# hotswap.net
KiCad netlist of a schematic drawn in EAGLE
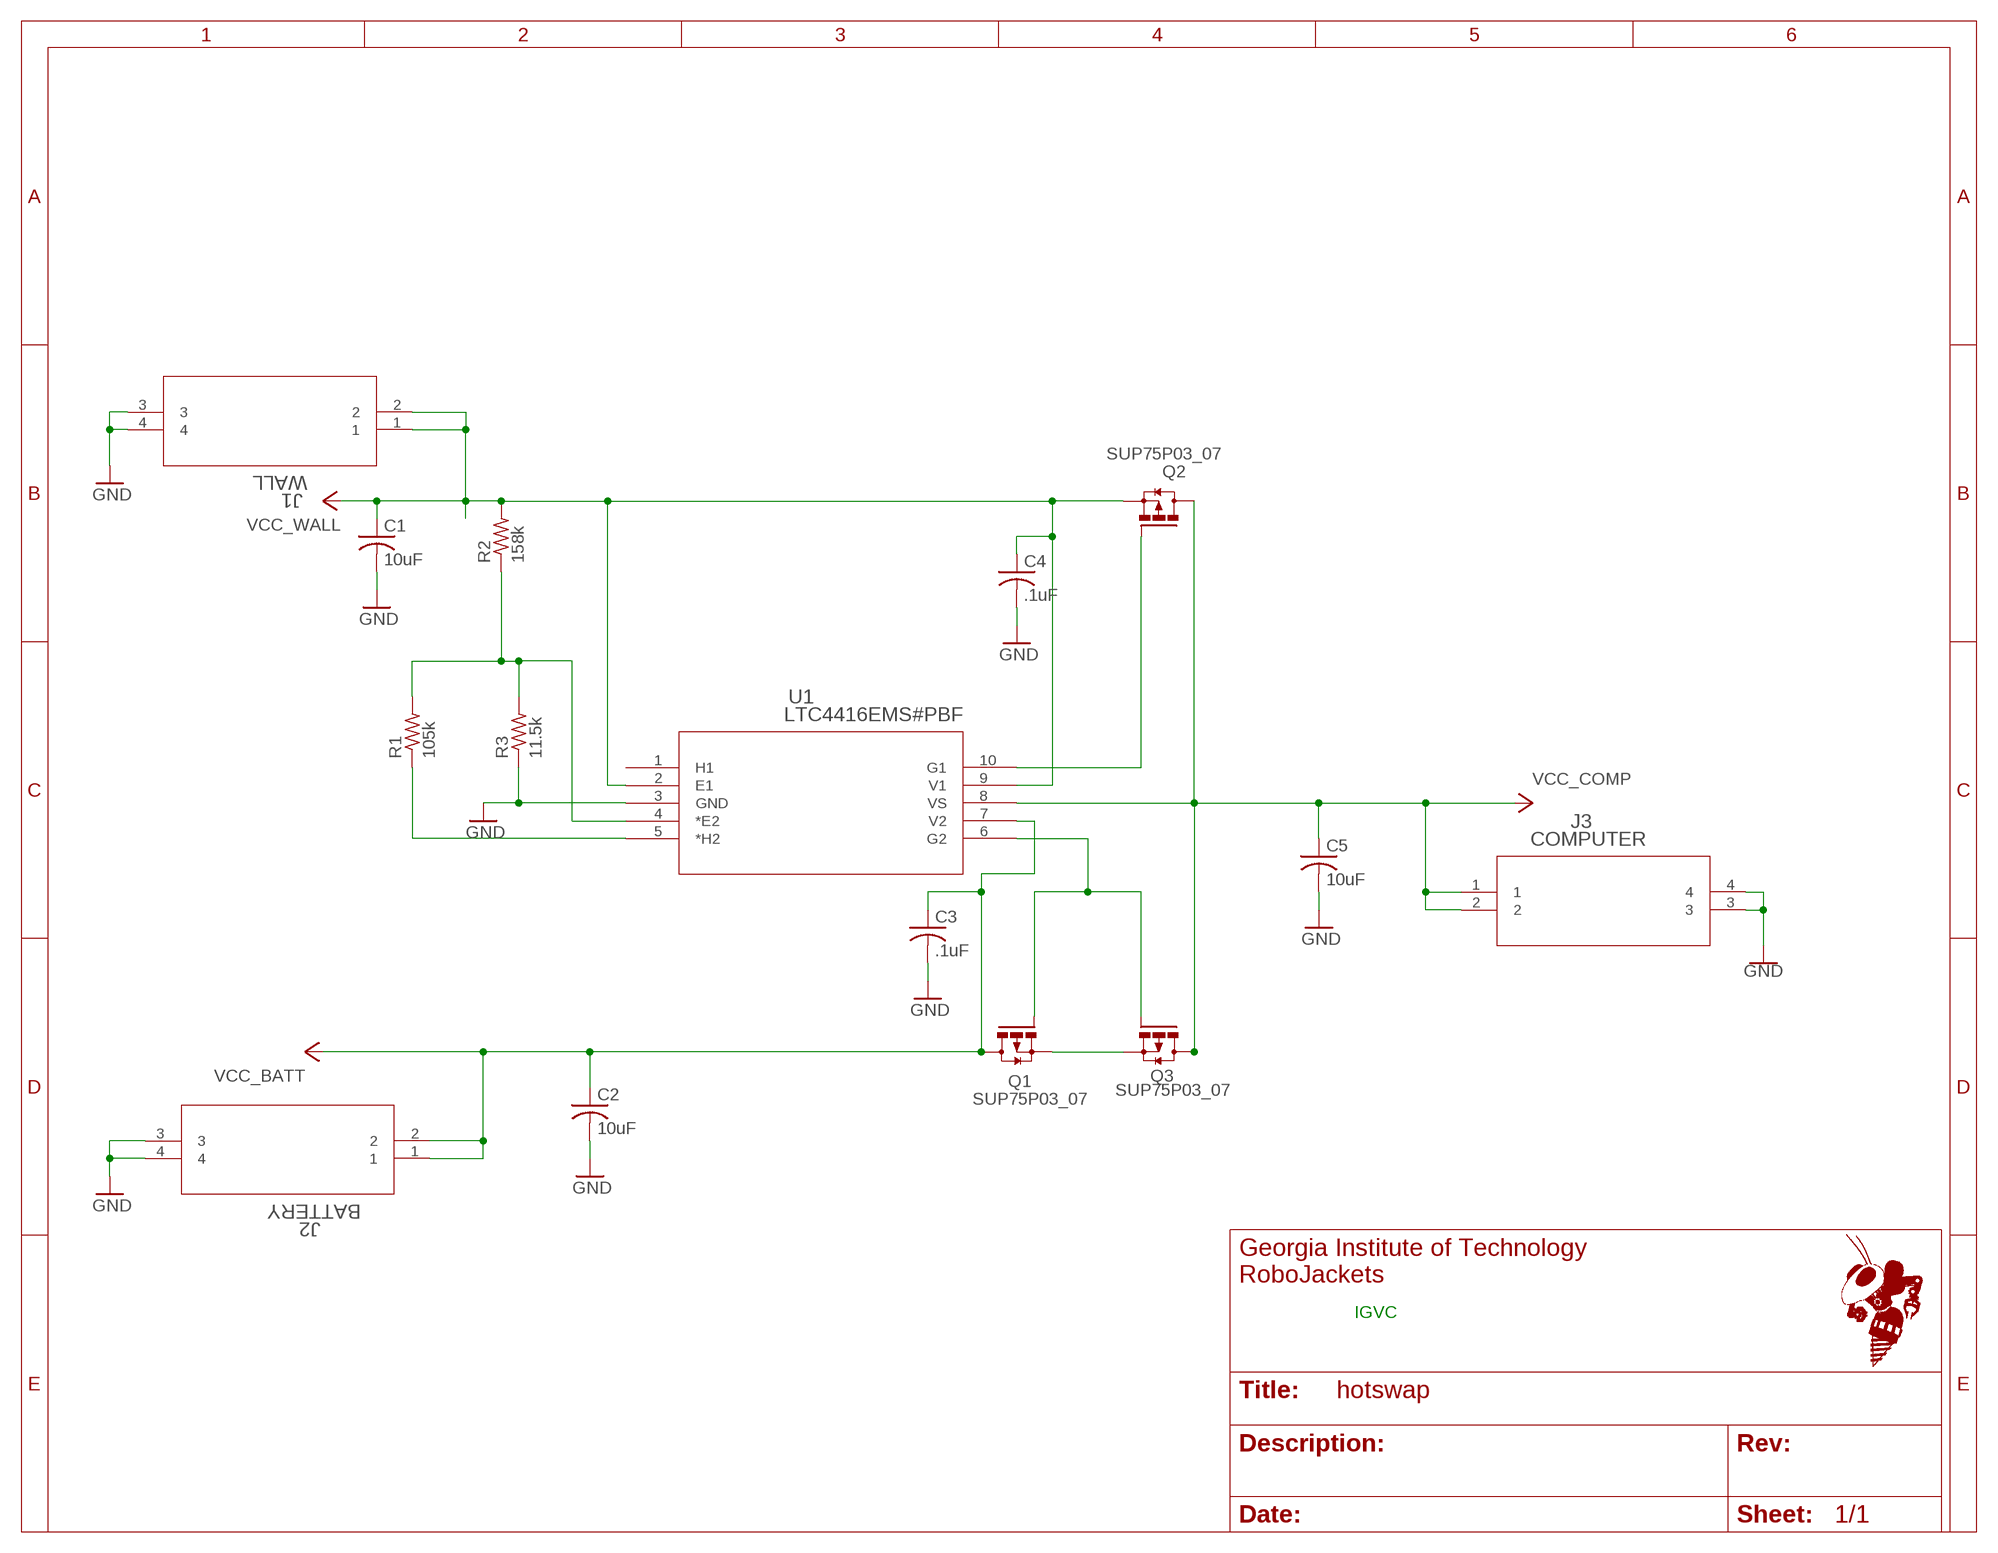
[diagram p0: schematic, sheet 1]

(export (version "E")
  (design (tool "Eeschema 10.0.6"))
  (components
    (comp (ref "C1")
      (value "10uF")
      (footprint "eagle-import:C1210")
      (libsource (lib "eagle-import") (part "C-USC1210"))
    )
    (comp (ref "C2")
      (value "10uF")
      (footprint "eagle-import:C1210")
      (libsource (lib "eagle-import") (part "C-USC1210"))
    )
    (comp (ref "C3")
      (value ".1uF")
      (footprint "eagle-import:C0805")
      (libsource (lib "eagle-import") (part "C-USC0805"))
    )
    (comp (ref "C4")
      (value ".1uF")
      (footprint "eagle-import:C0805")
      (libsource (lib "eagle-import") (part "C-USC0805"))
    )
    (comp (ref "C5")
      (value "10uF")
      (footprint "eagle-import:C1210")
      (libsource (lib "eagle-import") (part "C-USC1210"))
    )
    (comp (ref "J1")
      (value "WALL")
      (footprint "eagle-import:641737-1")
      (fields (field (name "MANUFACTURER_PART_NUMBER") "6417371"))
      (libsource (lib "eagle-import") (part "641737-1"))
    )
    (comp (ref "J2")
      (value "BATTERY")
      (footprint "eagle-import:641737-1")
      (fields (field (name "MANUFACTURER_PART_NUMBER") "6417371"))
      (libsource (lib "eagle-import") (part "641737-1"))
    )
    (comp (ref "J3")
      (value "COMPUTER")
      (footprint "eagle-import:641737-1")
      (fields (field (name "MANUFACTURER_PART_NUMBER") "6417371"))
      (libsource (lib "eagle-import") (part "641737-1"))
    )
    (comp (ref "Q1")
      (value "SUP75P03_07")
      (footprint "eagle-import:DPACK_2")
      (libsource (lib "eagle-import") (part "SUP75P03_07"))
    )
    (comp (ref "Q2")
      (value "SUP75P03_07")
      (footprint "eagle-import:DPACK_2")
      (libsource (lib "eagle-import") (part "SUP75P03_07"))
    )
    (comp (ref "Q3")
      (value "SUP75P03_07")
      (footprint "eagle-import:DPACK_2")
      (libsource (lib "eagle-import") (part "SUP75P03_07"))
    )
    (comp (ref "R1")
      (value "105k")
      (footprint "eagle-import:R0603")
      (libsource (lib "eagle-import") (part "R-US_R0603"))
    )
    (comp (ref "R2")
      (value "158k")
      (footprint "eagle-import:R0603")
      (libsource (lib "eagle-import") (part "R-US_R0603"))
    )
    (comp (ref "R3")
      (value "11.5k")
      (footprint "eagle-import:R0603")
      (libsource (lib "eagle-import") (part "R-US_R0603"))
    )
    (comp (ref "U1")
      (value "LTC4416EMS#PBF")
      (footprint "eagle-import:MSOP-10_MS")
      (fields
        (field (name "DIGI-KEY_PART_NUMBER") "LTC4416EMS#PBF-ND")
        (field (name "MF") "Linear Technology")
      )
      (libsource (lib "eagle-import") (part "LTC4416EMS#PBF"))
    )
  )
  (nets
    (net (code "1") (name "GND") (class "Default")
      (node (ref "C1") (pin "2") (pinfunction "2_2") (pintype "passive"))
      (node (ref "C2") (pin "2") (pinfunction "2_2") (pintype "passive"))
      (node (ref "C3") (pin "2") (pinfunction "2_2") (pintype "passive"))
      (node (ref "C4") (pin "2") (pinfunction "2_2") (pintype "passive"))
      (node (ref "C5") (pin "2") (pinfunction "2_2") (pintype "passive"))
      (node (ref "J1") (pin "3") (pinfunction "3_3") (pintype "passive"))
      (node (ref "J1") (pin "4") (pinfunction "4_4") (pintype "passive"))
      (node (ref "J2") (pin "3") (pinfunction "3_3") (pintype "passive"))
      (node (ref "J2") (pin "4") (pinfunction "4_4") (pintype "passive"))
      (node (ref "J3") (pin "3") (pinfunction "3_3") (pintype "passive"))
      (node (ref "J3") (pin "4") (pinfunction "4_4") (pintype "passive"))
      (node (ref "R3") (pin "1") (pinfunction "1_1") (pintype "passive"))
      (node (ref "U1") (pin "3") (pinfunction "GND_3") (pintype "power_in"))
    )
    (net (code "2") (name "Net-(Q1-PadS)") (class "Default")
      (node (ref "Q1") (pin "S") (pinfunction "S_S") (pintype "passive"))
      (node (ref "Q3") (pin "S") (pinfunction "S_S") (pintype "passive"))
    )
    (net (code "3") (name "Net-(U1-*E2)") (class "Default")
      (node (ref "R1") (pin "2") (pinfunction "2_2") (pintype "passive"))
      (node (ref "R2") (pin "1") (pinfunction "1_1") (pintype "passive"))
      (node (ref "R3") (pin "2") (pinfunction "2_2") (pintype "passive"))
      (node (ref "U1") (pin "4") (pinfunction "*E2_4") (pintype "input"))
    )
    (net (code "4") (name "Net-(U1-*H2)") (class "Default")
      (node (ref "R1") (pin "1") (pinfunction "1_1") (pintype "passive"))
      (node (ref "U1") (pin "5") (pinfunction "*H2_5") (pintype "input"))
    )
    (net (code "5") (name "Net-(U1-G1)") (class "Default")
      (node (ref "Q2") (pin "G") (pinfunction "G_G") (pintype "passive"))
      (node (ref "U1") (pin "10") (pinfunction "G1_10") (pintype "passive"))
    )
    (net (code "6") (name "Net-(U1-G2)") (class "Default")
      (node (ref "Q1") (pin "G") (pinfunction "G_G") (pintype "passive"))
      (node (ref "Q3") (pin "G") (pinfunction "G_G") (pintype "passive"))
      (node (ref "U1") (pin "6") (pinfunction "G2_6") (pintype "passive"))
    )
    (net (code "7") (name "VCC_BATT") (class "Default")
      (node (ref "C2") (pin "1") (pinfunction "1_1") (pintype "passive"))
      (node (ref "C3") (pin "1") (pinfunction "1_1") (pintype "passive"))
      (node (ref "J2") (pin "1") (pinfunction "1_1") (pintype "passive"))
      (node (ref "J2") (pin "2") (pinfunction "2_2") (pintype "passive"))
      (node (ref "Q1") (pin "D") (pinfunction "D_D") (pintype "passive"))
      (node (ref "U1") (pin "7") (pinfunction "V2_7") (pintype "input"))
    )
    (net (code "8") (name "VCC_COMP") (class "Default")
      (node (ref "C5") (pin "1") (pinfunction "1_1") (pintype "passive"))
      (node (ref "J3") (pin "1") (pinfunction "1_1") (pintype "passive"))
      (node (ref "J3") (pin "2") (pinfunction "2_2") (pintype "passive"))
      (node (ref "Q2") (pin "D") (pinfunction "D_D") (pintype "passive"))
      (node (ref "Q3") (pin "D") (pinfunction "D_D") (pintype "passive"))
      (node (ref "U1") (pin "8") (pinfunction "VS_8") (pintype "input"))
    )
    (net (code "9") (name "VCC_WALL") (class "Default")
      (node (ref "C1") (pin "1") (pinfunction "1_1") (pintype "passive"))
      (node (ref "C4") (pin "1") (pinfunction "1_1") (pintype "passive"))
      (node (ref "J1") (pin "1") (pinfunction "1_1") (pintype "passive"))
      (node (ref "J1") (pin "2") (pinfunction "2_2") (pintype "passive"))
      (node (ref "Q2") (pin "S") (pinfunction "S_S") (pintype "passive"))
      (node (ref "R2") (pin "2") (pinfunction "2_2") (pintype "passive"))
      (node (ref "U1") (pin "2") (pinfunction "E1_2") (pintype "input"))
      (node (ref "U1") (pin "9") (pinfunction "V1_9") (pintype "input"))
    )
    (net (code "10") (name "unconnected-(U1-H1-Pad1)") (class "Default")
      (node (ref "U1") (pin "1") (pinfunction "H1_1") (pintype "output"))
    )
  )
)
